# schematic.net
KiCad netlist of a schematic drawn in EAGLE
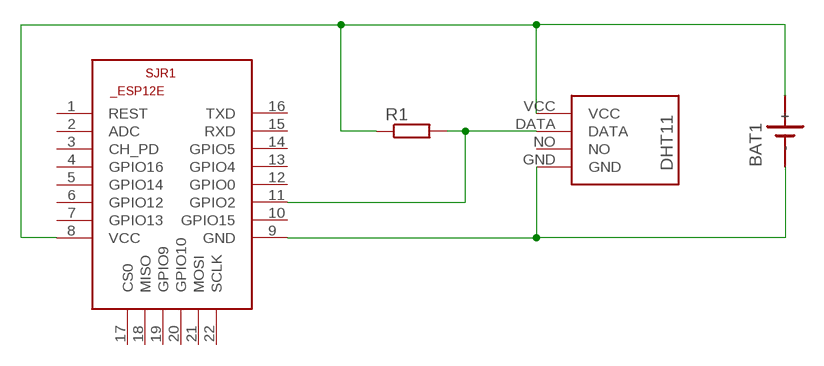
[diagram p0: schematic, sheet 1]

(export (version "E")
  (design (tool "Eeschema 10.0.6"))
  (components
    (comp (ref "BAT1")
      (value "SN2032")
      (footprint "eagle-import:SN2032")
      (libsource (lib "eagle-import") (part "SN2032"))
    )
    (comp (ref "R1")
      (value "10 kΩ")
      (footprint "eagle-import:0207_10")
      (libsource (lib "eagle-import") (part "R-EU_0207/10"))
    )
    (comp (ref "SJR1")
      (value "ESP8266-12EESP12E")
      (footprint "eagle-import:ESP8266-ESP12E")
      (libsource (lib "eagle-import") (part "ESP8266-12EESP12E"))
    )
    (comp (ref "U$2")
      (value "DHT11")
      (footprint "eagle-import:DHT11")
      (libsource (lib "eagle-import") (part "DHT11"))
    )
  )
  (nets
    (net (code "1") (name "Net-(SJR1-GND)") (class "Default")
      (node (ref "BAT1") (pin "-") (pinfunction "-_-") (pintype "passive"))
      (node (ref "SJR1") (pin "9") (pinfunction "GND_9") (pintype "bidirectional"))
      (node (ref "U$2") (pin "GND") (pinfunction "GND_GND") (pintype "bidirectional"))
    )
    (net (code "2") (name "Net-(SJR1-GPIO2)") (class "Default")
      (node (ref "R1") (pin "2") (pinfunction "2_2") (pintype "passive"))
      (node (ref "SJR1") (pin "11") (pinfunction "GPIO2_11") (pintype "bidirectional"))
      (node (ref "U$2") (pin "DATA") (pinfunction "DATA_DATA") (pintype "bidirectional"))
    )
    (net (code "3") (name "Net-(SJR1-VCC)") (class "Default")
      (node (ref "BAT1") (pin "+") (pinfunction "+_+") (pintype "passive"))
      (node (ref "R1") (pin "1") (pinfunction "1_1") (pintype "passive"))
      (node (ref "SJR1") (pin "8") (pinfunction "VCC_8") (pintype "bidirectional"))
      (node (ref "U$2") (pin "VCC") (pinfunction "VCC_VCC") (pintype "bidirectional"))
    )
    (net (code "4") (name "unconnected-(SJR1-ADC-Pad2)") (class "Default")
      (node (ref "SJR1") (pin "2") (pinfunction "ADC_2") (pintype "bidirectional"))
    )
    (net (code "5") (name "unconnected-(SJR1-CH_PD-Pad3)") (class "Default")
      (node (ref "SJR1") (pin "3") (pinfunction "CH_PD_3") (pintype "bidirectional"))
    )
    (net (code "6") (name "unconnected-(SJR1-CS0-Pad17)") (class "Default")
      (node (ref "SJR1") (pin "17") (pinfunction "CS0_17") (pintype "bidirectional"))
    )
    (net (code "7") (name "unconnected-(SJR1-GPIO0-Pad12)") (class "Default")
      (node (ref "SJR1") (pin "12") (pinfunction "GPIO0_12") (pintype "bidirectional"))
    )
    (net (code "8") (name "unconnected-(SJR1-GPIO4-Pad13)") (class "Default")
      (node (ref "SJR1") (pin "13") (pinfunction "GPIO4_13") (pintype "bidirectional"))
    )
    (net (code "9") (name "unconnected-(SJR1-GPIO5-Pad14)") (class "Default")
      (node (ref "SJR1") (pin "14") (pinfunction "GPIO5_14") (pintype "bidirectional"))
    )
    (net (code "10") (name "unconnected-(SJR1-GPIO9-Pad19)") (class "Default")
      (node (ref "SJR1") (pin "19") (pinfunction "GPIO9_19") (pintype "bidirectional"))
    )
    (net (code "11") (name "unconnected-(SJR1-GPIO10-Pad20)") (class "Default")
      (node (ref "SJR1") (pin "20") (pinfunction "GPIO10_20") (pintype "bidirectional"))
    )
    (net (code "12") (name "unconnected-(SJR1-GPIO12-Pad6)") (class "Default")
      (node (ref "SJR1") (pin "6") (pinfunction "GPIO12_6") (pintype "bidirectional"))
    )
    (net (code "13") (name "unconnected-(SJR1-GPIO13-Pad7)") (class "Default")
      (node (ref "SJR1") (pin "7") (pinfunction "GPIO13_7") (pintype "bidirectional"))
    )
    (net (code "14") (name "unconnected-(SJR1-GPIO14-Pad5)") (class "Default")
      (node (ref "SJR1") (pin "5") (pinfunction "GPIO14_5") (pintype "bidirectional"))
    )
    (net (code "15") (name "unconnected-(SJR1-GPIO15-Pad10)") (class "Default")
      (node (ref "SJR1") (pin "10") (pinfunction "GPIO15_10") (pintype "bidirectional"))
    )
    (net (code "16") (name "unconnected-(SJR1-GPIO16-Pad4)") (class "Default")
      (node (ref "SJR1") (pin "4") (pinfunction "GPIO16_4") (pintype "bidirectional"))
    )
    (net (code "17") (name "unconnected-(SJR1-MISO-Pad18)") (class "Default")
      (node (ref "SJR1") (pin "18") (pinfunction "MISO_18") (pintype "bidirectional"))
    )
    (net (code "18") (name "unconnected-(SJR1-MOSI-Pad21)") (class "Default")
      (node (ref "SJR1") (pin "21") (pinfunction "MOSI_21") (pintype "bidirectional"))
    )
    (net (code "19") (name "unconnected-(SJR1-REST-Pad1)") (class "Default")
      (node (ref "SJR1") (pin "1") (pinfunction "REST_1") (pintype "bidirectional"))
    )
    (net (code "20") (name "unconnected-(SJR1-RXD-Pad15)") (class "Default")
      (node (ref "SJR1") (pin "15") (pinfunction "RXD_15") (pintype "bidirectional"))
    )
    (net (code "21") (name "unconnected-(SJR1-SCLK-Pad22)") (class "Default")
      (node (ref "SJR1") (pin "22") (pinfunction "SCLK_22") (pintype "bidirectional"))
    )
    (net (code "22") (name "unconnected-(SJR1-TXD-Pad16)") (class "Default")
      (node (ref "SJR1") (pin "16") (pinfunction "TXD_16") (pintype "bidirectional"))
    )
    (net (code "23") (name "unconnected-(U$2-PadNO)") (class "Default")
      (node (ref "U$2") (pin "NO") (pinfunction "NO_NO") (pintype "bidirectional"))
    )
  )
)
